# Periph.net
KiCad netlist of a schematic drawn in Altium Designer
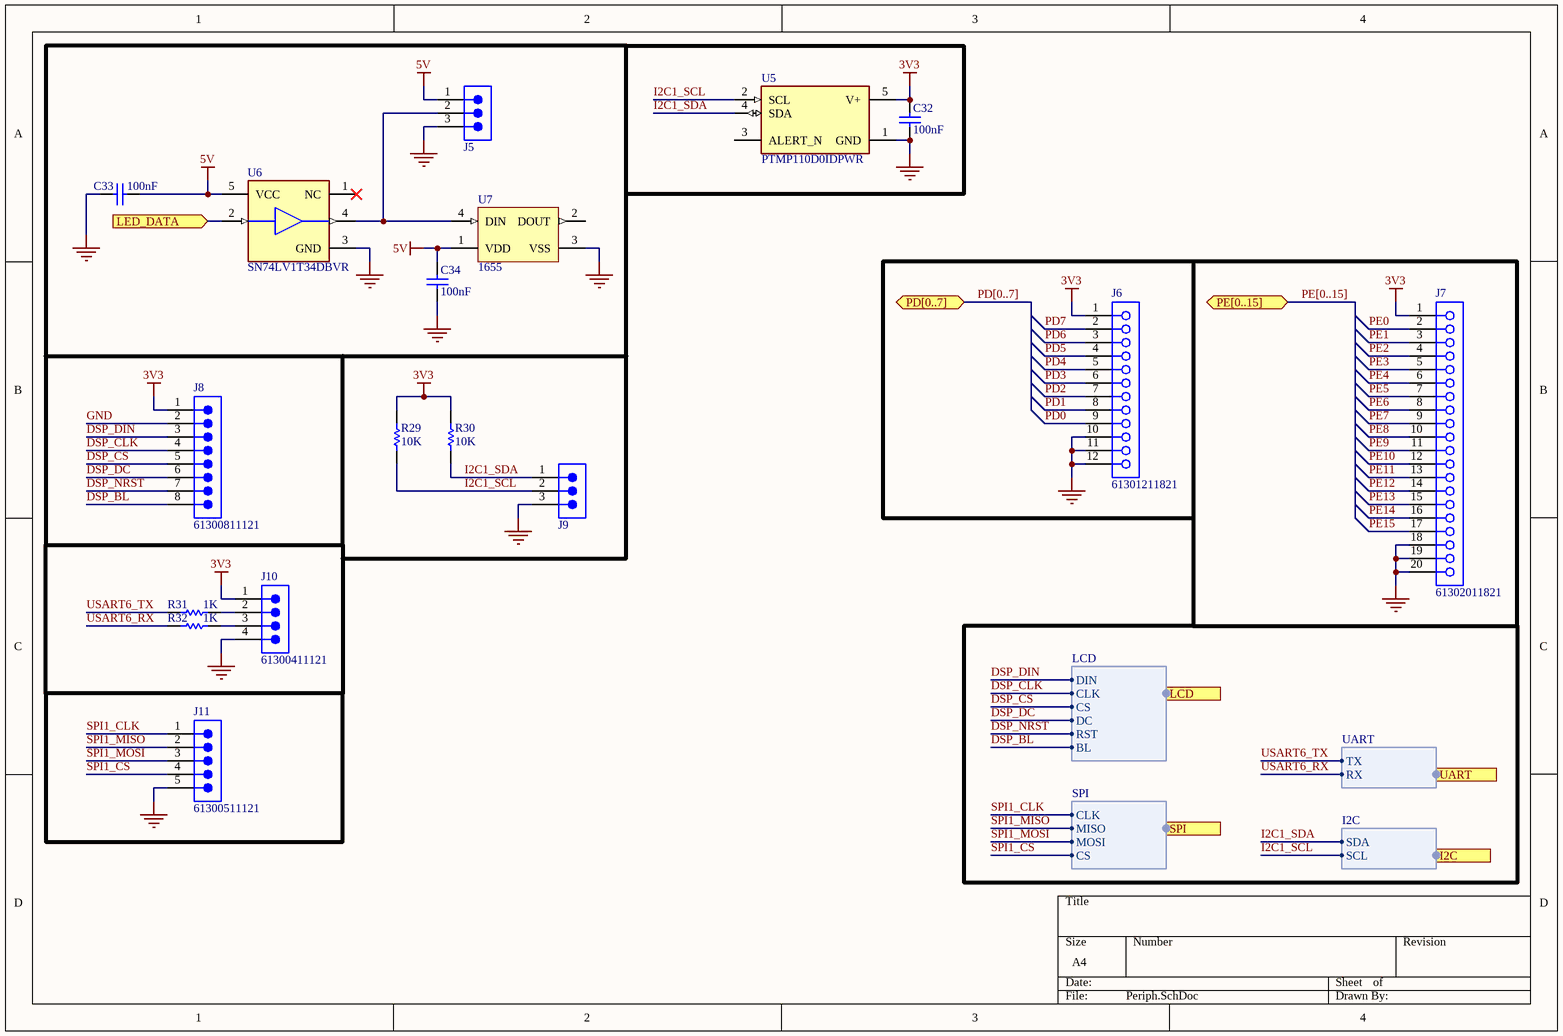
[diagram p0: Periph.SchDoc]

(export (version "E")
  (design (tool "Eeschema 10.0.6"))
  (components
    (comp (ref "C32")
      (value "100nF")
      (footprint "0603")
      (description "Capacitor 100V \r\n0603")
      (libsource (lib "Schlib1") (part "C0603C104K1RACAUTO"))
    )
    (comp (ref "C33")
      (value "100nF")
      (footprint "0603")
      (description "Capacitor 100V \r\n0603")
      (libsource (lib "Schlib1") (part "C0603C104K1RACAUTO"))
    )
    (comp (ref "C34")
      (value "100nF")
      (footprint "0603")
      (description "Capacitor 100V \r\n0603")
      (libsource (lib "Schlib1") (part "C0603C104K1RACAUTO"))
    )
    (comp (ref "J5")
      (value "61300311121")
      (footprint "61300311121")
      (libsource (lib "Altium Content Vault") (part "Header_Male_1R_03P"))
    )
    (comp (ref "J6")
      (value "61301211821")
      (footprint "61301211821")
      (libsource (lib "Altium Content Vault") (part "Header_Female_1R_12P"))
    )
    (comp (ref "J7")
      (value "61302011821")
      (footprint "61302011821")
      (libsource (lib "Altium Content Vault") (part "Header_Female_1R_20P"))
    )
    (comp (ref "J8")
      (value "61300811121")
      (footprint "61300811121")
      (libsource (lib "Altium Content Vault") (part "Header_Male_1R_08P"))
    )
    (comp (ref "J9")
      (value "61300311121")
      (footprint "61300311121")
      (libsource (lib "Altium Content Vault") (part "Header_Male_1R_03P"))
    )
    (comp (ref "J10")
      (value "61300411121")
      (footprint "61300411121")
      (libsource (lib "Altium Content Vault") (part "Header_Male_1R_04P"))
    )
    (comp (ref "J11")
      (value "61300511121")
      (footprint "61300511121")
      (libsource (lib "Altium Content Vault") (part "Header_Male_1R_05P"))
    )
    (comp (ref "R29")
      (value "10K")
      (footprint "0603")
      (description "Resistor 0.1W")
      (libsource (lib "Schlib1") (part "CRCW060310K0FKEA"))
    )
    (comp (ref "R30")
      (value "10K")
      (footprint "0603")
      (description "Resistor 0.1W")
      (libsource (lib "Schlib1") (part "CRCW060310K0FKEA"))
    )
    (comp (ref "R31")
      (value "1K")
      (footprint "0603")
      (description "Resistor 0.1W")
      (libsource (lib "Schlib1") (part "CRCW06031K00FKEA"))
    )
    (comp (ref "R32")
      (value "1K")
      (footprint "0603")
      (description "Resistor 0.1W")
      (libsource (lib "Schlib1") (part "CRCW06031K00FKEA"))
    )
    (comp (ref "U5")
      (value "PTMP110D0IDPWR")
      (footprint "DPW0005A-MFG")
      (description "No Description Available")
      (libsource (lib "Schlib1") (part "PTMP110D0IDPWR"))
    )
    (comp (ref "U6")
      (value "SN74LV1T34DBVR")
      (footprint "FP-DBV0005A-IPC_B")
      (description "IC BUF NON-INVERT 5.5V SOT23-5")
      (libsource (lib "Altium Content Vault") (part "d03805866fcc65e5014dff611fc4129"))
    )
    (comp (ref "U7")
      (value "1655")
      (footprint "ADA-RGB-1655_V")
      (fields (field (name "MANUFACTURER") "Adafruit-Industries-LLC"))
      (libsource (lib "Altium Content Vault") (part "ADA-RGB-1655-4"))
    )
  )
  (nets
    (net (code "5") (name "/DSP_BL") (class "Default")
      (node (ref "J8") (pin "8") (pinfunction "8_8") (pintype "passive"))
    )
    (net (code "6") (name "/DSP_CLK") (class "Default")
      (node (ref "J8") (pin "4") (pinfunction "4_4") (pintype "passive"))
    )
    (net (code "7") (name "/DSP_CS") (class "Default")
      (node (ref "J8") (pin "5") (pinfunction "5_5") (pintype "passive"))
    )
    (net (code "8") (name "/DSP_DC") (class "Default")
      (node (ref "J8") (pin "6") (pinfunction "6_6") (pintype "passive"))
    )
    (net (code "9") (name "/DSP_DIN") (class "Default")
      (node (ref "J8") (pin "3") (pinfunction "3_3") (pintype "passive"))
    )
    (net (code "10") (name "/DSP_NRST") (class "Default")
      (node (ref "J8") (pin "7") (pinfunction "7_7") (pintype "passive"))
    )
    (net (code "11") (name "/I2C1_SCL") (class "Default")
      (node (ref "J9") (pin "2") (pinfunction "2_2") (pintype "passive"))
      (node (ref "R29") (pin "1") (pinfunction "1_1") (pintype "passive"))
      (node (ref "U5") (pin "2") (pinfunction "SCL_2") (pintype "input"))
    )
    (net (code "12") (name "/I2C1_SDA") (class "Default")
      (node (ref "J9") (pin "1") (pinfunction "1_1") (pintype "passive"))
      (node (ref "R30") (pin "1") (pinfunction "1_1") (pintype "passive"))
      (node (ref "U5") (pin "4") (pinfunction "SDA_4") (pintype "bidirectional"))
    )
    (net (code "13") (name "/LED_DATA") (class "Default")
      (node (ref "U6") (pin "2") (pinfunction "A_2") (pintype "input"))
    )
    (net (code "14") (name "/PD0") (class "Default")
      (node (ref "J6") (pin "9") (pinfunction "9_9") (pintype "passive"))
    )
    (net (code "15") (name "/PD1") (class "Default")
      (node (ref "J6") (pin "8") (pinfunction "8_8") (pintype "passive"))
    )
    (net (code "16") (name "/PD2") (class "Default")
      (node (ref "J6") (pin "7") (pinfunction "7_7") (pintype "passive"))
    )
    (net (code "17") (name "/PD3") (class "Default")
      (node (ref "J6") (pin "6") (pinfunction "6_6") (pintype "passive"))
    )
    (net (code "18") (name "/PD4") (class "Default")
      (node (ref "J6") (pin "5") (pinfunction "5_5") (pintype "passive"))
    )
    (net (code "19") (name "/PD5") (class "Default")
      (node (ref "J6") (pin "4") (pinfunction "4_4") (pintype "passive"))
    )
    (net (code "20") (name "/PD6") (class "Default")
      (node (ref "J6") (pin "3") (pinfunction "3_3") (pintype "passive"))
    )
    (net (code "21") (name "/PD7") (class "Default")
      (node (ref "J6") (pin "2") (pinfunction "2_2") (pintype "passive"))
    )
    (net (code "23") (name "/PE0") (class "Default")
      (node (ref "J7") (pin "2") (pinfunction "2_2") (pintype "passive"))
    )
    (net (code "24") (name "/PE1") (class "Default")
      (node (ref "J7") (pin "3") (pinfunction "3_3") (pintype "passive"))
    )
    (net (code "25") (name "/PE2") (class "Default")
      (node (ref "J7") (pin "4") (pinfunction "4_4") (pintype "passive"))
    )
    (net (code "26") (name "/PE3") (class "Default")
      (node (ref "J7") (pin "5") (pinfunction "5_5") (pintype "passive"))
    )
    (net (code "27") (name "/PE4") (class "Default")
      (node (ref "J7") (pin "6") (pinfunction "6_6") (pintype "passive"))
    )
    (net (code "28") (name "/PE5") (class "Default")
      (node (ref "J7") (pin "7") (pinfunction "7_7") (pintype "passive"))
    )
    (net (code "29") (name "/PE6") (class "Default")
      (node (ref "J7") (pin "8") (pinfunction "8_8") (pintype "passive"))
    )
    (net (code "30") (name "/PE7") (class "Default")
      (node (ref "J7") (pin "9") (pinfunction "9_9") (pintype "passive"))
    )
    (net (code "31") (name "/PE8") (class "Default")
      (node (ref "J7") (pin "10") (pinfunction "10_10") (pintype "passive"))
    )
    (net (code "32") (name "/PE9") (class "Default")
      (node (ref "J7") (pin "11") (pinfunction "11_11") (pintype "passive"))
    )
    (net (code "33") (name "/PE10") (class "Default")
      (node (ref "J7") (pin "12") (pinfunction "12_12") (pintype "passive"))
    )
    (net (code "34") (name "/PE11") (class "Default")
      (node (ref "J7") (pin "13") (pinfunction "13_13") (pintype "passive"))
    )
    (net (code "35") (name "/PE12") (class "Default")
      (node (ref "J7") (pin "14") (pinfunction "14_14") (pintype "passive"))
    )
    (net (code "36") (name "/PE13") (class "Default")
      (node (ref "J7") (pin "15") (pinfunction "15_15") (pintype "passive"))
    )
    (net (code "37") (name "/PE14") (class "Default")
      (node (ref "J7") (pin "16") (pinfunction "16_16") (pintype "passive"))
    )
    (net (code "38") (name "/PE15") (class "Default")
      (node (ref "J7") (pin "17") (pinfunction "17_17") (pintype "passive"))
    )
    (net (code "40") (name "/SPI1_CLK") (class "Default")
      (node (ref "J11") (pin "1") (pinfunction "1_1") (pintype "passive"))
    )
    (net (code "41") (name "/SPI1_CS") (class "Default")
      (node (ref "J11") (pin "4") (pinfunction "4_4") (pintype "passive"))
    )
    (net (code "42") (name "/SPI1_MISO") (class "Default")
      (node (ref "J11") (pin "2") (pinfunction "2_2") (pintype "passive"))
    )
    (net (code "43") (name "/SPI1_MOSI") (class "Default")
      (node (ref "J11") (pin "3") (pinfunction "3_3") (pintype "passive"))
    )
    (net (code "44") (name "/USART6_RX") (class "Default")
      (node (ref "R32") (pin "1") (pinfunction "1_1") (pintype "passive"))
    )
    (net (code "45") (name "/USART6_TX") (class "Default")
      (node (ref "R31") (pin "1") (pinfunction "1_1") (pintype "passive"))
    )
    (net (code "50") (name "3V3") (class "Default")
      (node (ref "C32") (pin "1") (pinfunction "1_1") (pintype "passive"))
      (node (ref "J10") (pin "1") (pinfunction "1_1") (pintype "passive"))
      (node (ref "J6") (pin "1") (pinfunction "1_1") (pintype "passive"))
      (node (ref "J7") (pin "1") (pinfunction "1_1") (pintype "passive"))
      (node (ref "J8") (pin "1") (pinfunction "1_1") (pintype "passive"))
      (node (ref "R29") (pin "2") (pinfunction "2_2") (pintype "passive"))
      (node (ref "R30") (pin "2") (pinfunction "2_2") (pintype "passive"))
      (node (ref "U5") (pin "5") (pinfunction "V+_5") (pintype "power_in"))
    )
    (net (code "51") (name "5V") (class "Default")
      (node (ref "C33") (pin "2") (pinfunction "2_2") (pintype "passive"))
      (node (ref "C34") (pin "1") (pinfunction "1_1") (pintype "passive"))
      (node (ref "J5") (pin "1") (pinfunction "1_1") (pintype "passive"))
      (node (ref "U6") (pin "5") (pinfunction "VCC_5") (pintype "power_in"))
      (node (ref "U7") (pin "1") (pinfunction "VDD_1") (pintype "power_in"))
    )
    (net (code "52") (name "GND") (class "Default")
      (node (ref "C32") (pin "2") (pinfunction "2_2") (pintype "passive"))
      (node (ref "C33") (pin "1") (pinfunction "1_1") (pintype "passive"))
      (node (ref "C34") (pin "2") (pinfunction "2_2") (pintype "passive"))
      (node (ref "J10") (pin "4") (pinfunction "4_4") (pintype "passive"))
      (node (ref "J11") (pin "5") (pinfunction "5_5") (pintype "passive"))
      (node (ref "J5") (pin "3") (pinfunction "3_3") (pintype "passive"))
      (node (ref "J6") (pin "10") (pinfunction "10_10") (pintype "passive"))
      (node (ref "J6") (pin "11") (pinfunction "11_11") (pintype "passive"))
      (node (ref "J6") (pin "12") (pinfunction "12_12") (pintype "passive"))
      (node (ref "J7") (pin "18") (pinfunction "18_18") (pintype "passive"))
      (node (ref "J7") (pin "19") (pinfunction "19_19") (pintype "passive"))
      (node (ref "J7") (pin "20") (pinfunction "20_20") (pintype "passive"))
      (node (ref "J8") (pin "2") (pinfunction "2_2") (pintype "passive"))
      (node (ref "J9") (pin "3") (pinfunction "3_3") (pintype "passive"))
      (node (ref "U5") (pin "1") (pinfunction "GND_1") (pintype "power_in"))
      (node (ref "U6") (pin "3") (pinfunction "GND_3") (pintype "power_in"))
      (node (ref "U7") (pin "3") (pinfunction "VSS_3") (pintype "power_in"))
    )
    (net (code "53") (name "Net-(J10-Pad2)") (class "Default")
      (node (ref "J10") (pin "2") (pinfunction "2_2") (pintype "passive"))
      (node (ref "R31") (pin "2") (pinfunction "2_2") (pintype "passive"))
    )
    (net (code "54") (name "Net-(J10-Pad3)") (class "Default")
      (node (ref "J10") (pin "3") (pinfunction "3_3") (pintype "passive"))
      (node (ref "R32") (pin "2") (pinfunction "2_2") (pintype "passive"))
    )
    (net (code "55") (name "Net-(U6-Y)") (class "Default")
      (node (ref "J5") (pin "2") (pinfunction "2_2") (pintype "passive"))
      (node (ref "U6") (pin "4") (pinfunction "Y_4") (pintype "output"))
      (node (ref "U7") (pin "4") (pinfunction "DIN_4") (pintype "input"))
    )
    (net (code "56") (name "unconnected-(U5-ALERT_N-Pad3)") (class "Default")
      (node (ref "U5") (pin "3") (pinfunction "ALERT_N_3") (pintype "open_collector"))
    )
    (net (code "57") (name "unconnected-(U6-NC-Pad1)") (class "Default")
      (node (ref "U6") (pin "1") (pinfunction "NC_1") (pintype "passive+no_connect"))
    )
    (net (code "58") (name "unconnected-(U7-DOUT-Pad2)") (class "Default")
      (node (ref "U7") (pin "2") (pinfunction "DOUT_2") (pintype "output"))
    )
  )
)
